# Proiect_TSC.net
KiCad netlist of a schematic drawn in EAGLE
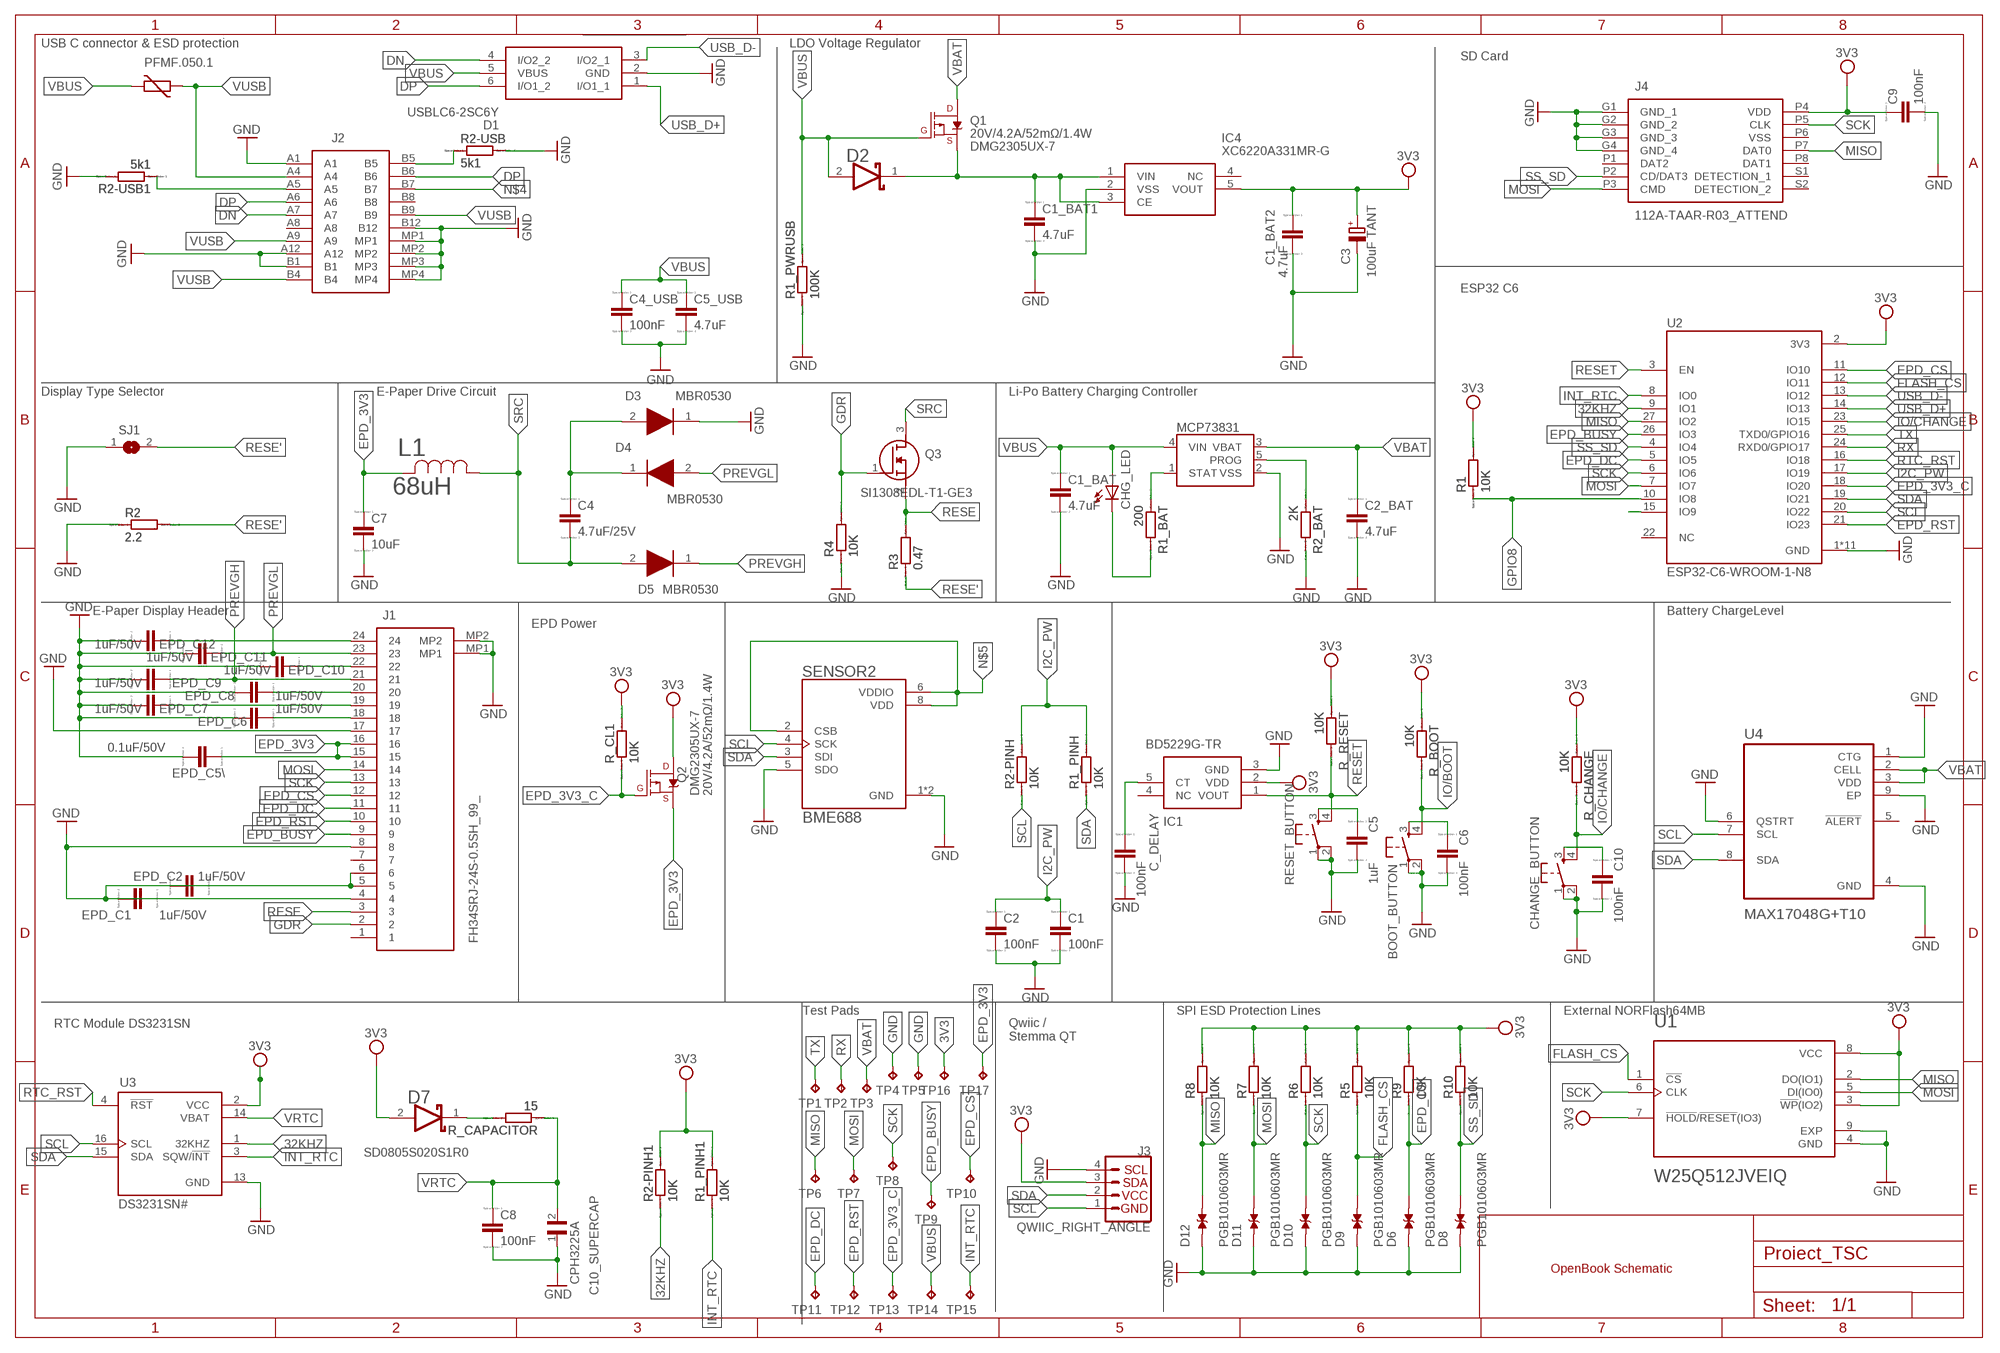
[diagram p0: schematic, sheet 1]

(export (version "E")
  (design (tool "Eeschema 10.0.6"))
  (components
    (comp (ref "BOOT_BUTTON")
      (value "BUTTON_CUSYOMV1")
      (footprint "eagle-import:MYBUTTON")
      (libsource (lib "eagle-import") (part "BUTTON_CUSYOMV1"))
    )
    (comp (ref "C1")
      (value "100nF")
      (footprint "eagle-import:ESP32_WROVER_EAGLE-LTSPICE_C0402")
      (libsource (lib "eagle-import") (part "ESP32_WROVER_EAGLE-LTSPICE_CC0402"))
    )
    (comp (ref "C1_BAT")
      (value "4.7uF")
      (footprint "eagle-import:ESP32_WROVER_EAGLE-LTSPICE_C0402")
      (libsource (lib "eagle-import") (part "ESP32_WROVER_EAGLE-LTSPICE_CC0402"))
    )
    (comp (ref "C1_BAT1")
      (value "4.7uF")
      (footprint "eagle-import:ESP32_WROVER_EAGLE-LTSPICE_C0402")
      (libsource (lib "eagle-import") (part "ESP32_WROVER_EAGLE-LTSPICE_CC0402"))
    )
    (comp (ref "C1_BAT2")
      (value "4.7uF")
      (footprint "eagle-import:ESP32_WROVER_EAGLE-LTSPICE_C0402")
      (libsource (lib "eagle-import") (part "ESP32_WROVER_EAGLE-LTSPICE_CC0402"))
    )
    (comp (ref "C2")
      (value "100nF")
      (footprint "eagle-import:ESP32_WROVER_EAGLE-LTSPICE_C0402")
      (libsource (lib "eagle-import") (part "ESP32_WROVER_EAGLE-LTSPICE_CC0402"))
    )
    (comp (ref "C2_BAT")
      (value "4.7uF")
      (footprint "eagle-import:ESP32_WROVER_EAGLE-LTSPICE_C0402")
      (libsource (lib "eagle-import") (part "ESP32_WROVER_EAGLE-LTSPICE_CC0402"))
    )
    (comp (ref "C3")
      (value "100uF TANT")
      (footprint "eagle-import:RCL_CT3528")
      (libsource (lib "eagle-import") (part "RCL_CPOL-EUCT3528"))
    )
    (comp (ref "C4")
      (value "4.7uF/25V")
      (footprint "eagle-import:ESP32_WROVER_EAGLE-LTSPICE_C0402")
      (libsource (lib "eagle-import") (part "ESP32_WROVER_EAGLE-LTSPICE_CC0402"))
    )
    (comp (ref "C4_USB")
      (value "100nF")
      (footprint "eagle-import:ESP32_WROVER_EAGLE-LTSPICE_C0402")
      (libsource (lib "eagle-import") (part "ESP32_WROVER_EAGLE-LTSPICE_CC0402"))
    )
    (comp (ref "C5")
      (value "1uF")
      (footprint "eagle-import:ESP32_WROVER_EAGLE-LTSPICE_C0402")
      (libsource (lib "eagle-import") (part "ESP32_WROVER_EAGLE-LTSPICE_CC0402"))
    )
    (comp (ref "C5_USB")
      (value "4.7uF")
      (footprint "eagle-import:ESP32_WROVER_EAGLE-LTSPICE_C0402")
      (libsource (lib "eagle-import") (part "ESP32_WROVER_EAGLE-LTSPICE_CC0402"))
    )
    (comp (ref "C6")
      (value "100nF")
      (footprint "eagle-import:ESP32_WROVER_EAGLE-LTSPICE_C0402")
      (libsource (lib "eagle-import") (part "ESP32_WROVER_EAGLE-LTSPICE_CC0402"))
    )
    (comp (ref "C7")
      (value "10uF")
      (footprint "eagle-import:ESP32_WROVER_EAGLE-LTSPICE_C0402")
      (libsource (lib "eagle-import") (part "ESP32_WROVER_EAGLE-LTSPICE_CC0402"))
    )
    (comp (ref "C8")
      (value "100nF")
      (footprint "eagle-import:ESP32_WROVER_EAGLE-LTSPICE_C0402")
      (libsource (lib "eagle-import") (part "ESP32_WROVER_EAGLE-LTSPICE_CC0402"))
    )
    (comp (ref "C9")
      (value "100nF")
      (footprint "eagle-import:ESP32_WROVER_EAGLE-LTSPICE_C0402")
      (libsource (lib "eagle-import") (part "ESP32_WROVER_EAGLE-LTSPICE_CC0402"))
    )
    (comp (ref "C10")
      (value "100nF")
      (footprint "eagle-import:ESP32_WROVER_EAGLE-LTSPICE_C0402")
      (libsource (lib "eagle-import") (part "ESP32_WROVER_EAGLE-LTSPICE_CC0402"))
    )
    (comp (ref "C10_SUPERCAP")
      (value "CPH3225A")
      (footprint "eagle-import:CAPCP3225X100N")
      (fields (field (name "MF") "Seiko Instruments"))
      (libsource (lib "eagle-import") (part "CPH3225A"))
    )
    (comp (ref "CHANGE_BUTTON")
      (value "BUTTON_CUSYOMV1")
      (footprint "eagle-import:MYBUTTON")
      (libsource (lib "eagle-import") (part "BUTTON_CUSYOMV1"))
    )
    (comp (ref "CHG_LED")
      (value "ADAFRUIT_LEDCHIP-LED0603")
      (footprint "eagle-import:ADAFRUIT_CHIP-LED0603")
      (libsource (lib "eagle-import") (part "ADAFRUIT_LEDCHIP-LED0603"))
    )
    (comp (ref "C_DELAY")
      (value "100nF")
      (footprint "eagle-import:ESP32_WROVER_EAGLE-LTSPICE_C0402")
      (libsource (lib "eagle-import") (part "ESP32_WROVER_EAGLE-LTSPICE_CC0402"))
    )
    (comp (ref "D1")
      (value "USBLC6-2SC6Y")
      (footprint "eagle-import:SOT95P280X145-6N")
      (fields (field (name "MF") "STMicroelectronics"))
      (libsource (lib "eagle-import") (part "USBLC6-2SC6Y"))
    )
    (comp (ref "D2")
      (value "ESP32_WROVER_AVX---SD0805S020S1R0_AVX_SD0805S020S1R0_0_0AVX_SD0805S020S1R0_0_0")
      (footprint "eagle-import:ESP32_WROVER_AVX---SD0805S020S1R0_AVX_SD0805S020S1R0_0")
      (fields
        (field (name "DIGIKEY_PART_NUMBER") "478-7800-1-ND")
        (field (name "MF") "AVX")
        (field (name "MOUSER_PART_NUMBER") "581-SD0805S020S1R0")
      )
      (libsource (lib "eagle-import") (part "ESP32_WROVER_AVX---SD0805S020S1R0_AVX_SD0805S020S1R0_0_0AVX_SD0805S020S1R0_0_0"))
    )
    (comp (ref "D3")
      (value "MBR0530")
      (footprint "eagle-import:SOD3716X135N")
      (fields (field (name "MF") "ON Semiconductor"))
      (libsource (lib "eagle-import") (part "MBR0530"))
    )
    (comp (ref "D4")
      (value "MBR0530")
      (footprint "eagle-import:SOD3716X135N")
      (fields (field (name "MF") "ON Semiconductor"))
      (libsource (lib "eagle-import") (part "MBR0530"))
    )
    (comp (ref "D5")
      (value "MBR0530")
      (footprint "eagle-import:SOD3716X135N")
      (fields (field (name "MF") "ON Semiconductor"))
      (libsource (lib "eagle-import") (part "MBR0530"))
    )
    (comp (ref "D6")
      (value "PGB1010603MR")
      (footprint "eagle-import:DIOC1608X36N")
      (fields (field (name "MF") "Littelfuse Inc."))
      (libsource (lib "eagle-import") (part "PGB1010603MR"))
    )
    (comp (ref "D7")
      (value "ESP32_WROVER_AVX---SD0805S020S1R0_AVX_SD0805S020S1R0_0_0AVX_SD0805S020S1R0_0_0")
      (footprint "eagle-import:ESP32_WROVER_AVX---SD0805S020S1R0_AVX_SD0805S020S1R0_0")
      (fields
        (field (name "DIGIKEY_PART_NUMBER") "478-7800-1-ND")
        (field (name "MF") "AVX")
        (field (name "MOUSER_PART_NUMBER") "581-SD0805S020S1R0")
      )
      (libsource (lib "eagle-import") (part "ESP32_WROVER_AVX---SD0805S020S1R0_AVX_SD0805S020S1R0_0_0AVX_SD0805S020S1R0_0_0"))
    )
    (comp (ref "D8")
      (value "PGB1010603MR")
      (footprint "eagle-import:DIOC1608X36N")
      (fields (field (name "MF") "Littelfuse Inc."))
      (libsource (lib "eagle-import") (part "PGB1010603MR"))
    )
    (comp (ref "D9")
      (value "PGB1010603MR")
      (footprint "eagle-import:DIOC1608X36N")
      (fields (field (name "MF") "Littelfuse Inc."))
      (libsource (lib "eagle-import") (part "PGB1010603MR"))
    )
    (comp (ref "D10")
      (value "PGB1010603MR")
      (footprint "eagle-import:DIOC1608X36N")
      (fields (field (name "MF") "Littelfuse Inc."))
      (libsource (lib "eagle-import") (part "PGB1010603MR"))
    )
    (comp (ref "D11")
      (value "PGB1010603MR")
      (footprint "eagle-import:DIOC1608X36N")
      (fields (field (name "MF") "Littelfuse Inc."))
      (libsource (lib "eagle-import") (part "PGB1010603MR"))
    )
    (comp (ref "D12")
      (value "PGB1010603MR")
      (footprint "eagle-import:DIOC1608X36N")
      (fields (field (name "MF") "Littelfuse Inc."))
      (libsource (lib "eagle-import") (part "PGB1010603MR"))
    )
    (comp (ref "EPD_C1")
      (value "1uF/50V")
      (footprint "eagle-import:ESP32_WROVER_EAGLE-LTSPICE_C0402")
      (libsource (lib "eagle-import") (part "ESP32_WROVER_EAGLE-LTSPICE_CC0402"))
    )
    (comp (ref "EPD_C2")
      (value "1uF/50V")
      (footprint "eagle-import:ESP32_WROVER_EAGLE-LTSPICE_C0402")
      (libsource (lib "eagle-import") (part "ESP32_WROVER_EAGLE-LTSPICE_CC0402"))
    )
    (comp (ref "EPD_C5\\")
      (value "0.1uF/50V")
      (footprint "eagle-import:EAGLE-LTSPICE_C0402")
      (libsource (lib "eagle-import") (part "EAGLE-LTSPICE_CC0402"))
    )
    (comp (ref "EPD_C6")
      (value "1uF/50V")
      (footprint "eagle-import:EAGLE-LTSPICE_C0402")
      (libsource (lib "eagle-import") (part "EAGLE-LTSPICE_CC0402"))
    )
    (comp (ref "EPD_C7")
      (value "1uF/50V")
      (footprint "eagle-import:EAGLE-LTSPICE_C0402")
      (libsource (lib "eagle-import") (part "EAGLE-LTSPICE_CC0402"))
    )
    (comp (ref "EPD_C8")
      (value "1uF/50V")
      (footprint "eagle-import:EAGLE-LTSPICE_C0402")
      (libsource (lib "eagle-import") (part "EAGLE-LTSPICE_CC0402"))
    )
    (comp (ref "EPD_C9")
      (value "1uF/50V")
      (footprint "eagle-import:EAGLE-LTSPICE_C0402")
      (libsource (lib "eagle-import") (part "EAGLE-LTSPICE_CC0402"))
    )
    (comp (ref "EPD_C10")
      (value "1uF/50V")
      (footprint "eagle-import:EAGLE-LTSPICE_C0402")
      (libsource (lib "eagle-import") (part "EAGLE-LTSPICE_CC0402"))
    )
    (comp (ref "EPD_C11")
      (value "1uF/50V")
      (footprint "eagle-import:EAGLE-LTSPICE_C0402")
      (libsource (lib "eagle-import") (part "EAGLE-LTSPICE_CC0402"))
    )
    (comp (ref "EPD_C12")
      (value "1uF/50V")
      (footprint "eagle-import:EAGLE-LTSPICE_C0402")
      (libsource (lib "eagle-import") (part "EAGLE-LTSPICE_CC0402"))
    )
    (comp (ref "IC1")
      (value "BD5229G-TR")
      (footprint "eagle-import:SOT95P280X125-5N")
      (fields (field (name "MOUSER_PART_NUMBER") "755-BD5229G-TR"))
      (libsource (lib "eagle-import") (part "BD5229G-TR"))
    )
    (comp (ref "IC4")
      (value "XC6220A331MR-G")
      (footprint "eagle-import:SOT95P280X120-5N")
      (fields (field (name "MOUSER_PART_NUMBER") "865-XC6220A331MR-G"))
      (libsource (lib "eagle-import") (part "XC6220A331MR-G"))
    )
    (comp (ref "J1")
      (value "FH34SRJ-24S-0.5SH_99_")
      (footprint "eagle-import:FH34SRJ24S05SH99")
      (fields
        (field (name "MANUFACTURER_PART_NUMBER") "FH34SRJ-24S-0.5SH(99)")
        (field (name "MOUSER_PART_NUMBER") "798-FH34SRJ24S05SH99")
      )
      (libsource (lib "eagle-import") (part "FH34SRJ-24S-0.5SH_99_"))
    )
    (comp (ref "J2")
      (value "SAMACSYS_PARTS_USB4110-GF-A")
      (footprint "eagle-import:SAMACSYS_PARTS_USB4110GFA")
      (fields
        (field (name "MANUFACTURER_PART_NUMBER") "USB4110-GF-A")
        (field (name "MOUSER_PART_NUMBER") "640-USB4110-GF-A")
      )
      (libsource (lib "eagle-import") (part "SAMACSYS_PARTS_USB4110-GF-A"))
    )
    (comp (ref "J3")
      (value "QWIIC_RIGHT_ANGLE")
      (footprint "eagle-import:JST04_1MM_RA")
      (libsource (lib "eagle-import") (part "QWIIC_CONNECTORJS-1MM"))
    )
    (comp (ref "J4")
      (value "112A-TAAR-R03_ATTEND")
      (footprint "eagle-import:112ATAARR03ATTEND")
      (fields (field (name "MANUFACTURER_PART_NUMBER") "112A-TAAR-R03 ATTEND"))
      (libsource (lib "eagle-import") (part "112A-TAAR-R03_ATTEND"))
    )
    (comp (ref "L1")
      (value "68uH")
      (footprint "eagle-import:IND_4828-WE-TPC_WRE")
      (fields
        (field (name "MANUFACTURER_PART_NUMBER") "744043680")
        (field (name "COPYRIGHT") "Copyright (C) 2024 Ultra Librarian. All rights reserved.")
      )
      (libsource (lib "eagle-import") (part "744043680IND_4828-WE-TPC_WRE"))
    )
    (comp (ref "MCP73831")
      (value "ESP32_WROVER_SPARKFUN-IC-POWER_MCP73831")
      (footprint "eagle-import:ESP32_WROVER_SPARKFUN-IC-POWER_SOT23-5")
      (libsource (lib "eagle-import") (part "ESP32_WROVER_SPARKFUN-IC-POWER_MCP73831"))
    )
    (comp (ref "PFMF.050.1")
      (value "ESP32C6_VARISTORCN1812")
      (footprint "eagle-import:ESP32C6_VARISTOR_CT_CN1812")
      (libsource (lib "eagle-import") (part "ESP32C6_VARISTORCN1812"))
    )
    (comp (ref "Q1")
      (value "20V/4.2A/52mΩ/1.4W")
      (footprint "eagle-import:ESP32_WROVER_SPARKFUN-DISCRETESEMI_SOT23-3")
      (libsource (lib "eagle-import") (part "ESP32_WROVER_SPARKFUN-DISCRETESEMI_MOSFET_PCH-DMG2305UX-7"))
    )
    (comp (ref "Q2")
      (value "20V/4.2A/52mΩ/1.4W")
      (footprint "eagle-import:ESP32_WROVER_SPARKFUN-DISCRETESEMI_SOT23-3")
      (libsource (lib "eagle-import") (part "ESP32_WROVER_SPARKFUN-DISCRETESEMI_MOSFET_PCH-DMG2305UX-7"))
    )
    (comp (ref "Q3")
      (value "SI1308EDL-T1-GE3")
      (footprint "eagle-import:SOT65P210X110-3N")
      (fields (field (name "MF") "Vishay Siliconix"))
      (libsource (lib "eagle-import") (part "SI1308EDL-T1-GE3"))
    )
    (comp (ref "R1")
      (value "10K")
      (footprint "eagle-import:ESP32_WROVER_EAGLE-LTSPICE_R0402")
      (libsource (lib "eagle-import") (part "ESP32_WROVER_EAGLE-LTSPICE_RR0402"))
    )
    (comp (ref "R1_BAT")
      (value "200")
      (footprint "eagle-import:ESP32_WROVER_EAGLE-LTSPICE_R0402")
      (libsource (lib "eagle-import") (part "ESP32_WROVER_EAGLE-LTSPICE_RR0402"))
    )
    (comp (ref "R1_PINH")
      (value "10K")
      (footprint "eagle-import:ESP32_WROVER_EAGLE-LTSPICE_R0402")
      (libsource (lib "eagle-import") (part "ESP32_WROVER_EAGLE-LTSPICE_RR0402"))
    )
    (comp (ref "R1_PINH1")
      (value "10K")
      (footprint "eagle-import:ESP32_WROVER_EAGLE-LTSPICE_R0402")
      (libsource (lib "eagle-import") (part "ESP32_WROVER_EAGLE-LTSPICE_RR0402"))
    )
    (comp (ref "R1_PWRUSB")
      (value "100K")
      (footprint "eagle-import:ESP32_WROVER_EAGLE-LTSPICE_R0402")
      (libsource (lib "eagle-import") (part "ESP32_WROVER_EAGLE-LTSPICE_RR0402"))
    )
    (comp (ref "R2")
      (value "2.2")
      (footprint "eagle-import:ESP32_WROVER_EAGLE-LTSPICE_R0402")
      (libsource (lib "eagle-import") (part "ESP32_WROVER_EAGLE-LTSPICE_RR0402"))
    )
    (comp (ref "R2-PINH")
      (value "10K")
      (footprint "eagle-import:ESP32_WROVER_EAGLE-LTSPICE_R0402")
      (libsource (lib "eagle-import") (part "ESP32_WROVER_EAGLE-LTSPICE_RR0402"))
    )
    (comp (ref "R2-PINH1")
      (value "10K")
      (footprint "eagle-import:ESP32_WROVER_EAGLE-LTSPICE_R0402")
      (libsource (lib "eagle-import") (part "ESP32_WROVER_EAGLE-LTSPICE_RR0402"))
    )
    (comp (ref "R2-USB")
      (value "5k1")
      (footprint "eagle-import:ESP32_WROVER_EAGLE-LTSPICE_R0402")
      (libsource (lib "eagle-import") (part "ESP32_WROVER_EAGLE-LTSPICE_RR0402"))
    )
    (comp (ref "R2-USB1")
      (value "5k1")
      (footprint "eagle-import:ESP32_WROVER_EAGLE-LTSPICE_R0402")
      (libsource (lib "eagle-import") (part "ESP32_WROVER_EAGLE-LTSPICE_RR0402"))
    )
    (comp (ref "R2_BAT")
      (value "2K")
      (footprint "eagle-import:ESP32_WROVER_EAGLE-LTSPICE_R0402")
      (libsource (lib "eagle-import") (part "ESP32_WROVER_EAGLE-LTSPICE_RR0402"))
    )
    (comp (ref "R3")
      (value "0.47")
      (footprint "eagle-import:ESP32_WROVER_EAGLE-LTSPICE_R0402")
      (libsource (lib "eagle-import") (part "ESP32_WROVER_EAGLE-LTSPICE_RR0402"))
    )
    (comp (ref "R4")
      (value "10K")
      (footprint "eagle-import:ESP32_WROVER_EAGLE-LTSPICE_R0402")
      (libsource (lib "eagle-import") (part "ESP32_WROVER_EAGLE-LTSPICE_RR0402"))
    )
    (comp (ref "R5")
      (value "10K")
      (footprint "eagle-import:ESP32_WROVER_EAGLE-LTSPICE_R0402")
      (libsource (lib "eagle-import") (part "ESP32_WROVER_EAGLE-LTSPICE_RR0402"))
    )
    (comp (ref "R6")
      (value "10K")
      (footprint "eagle-import:ESP32_WROVER_EAGLE-LTSPICE_R0402")
      (libsource (lib "eagle-import") (part "ESP32_WROVER_EAGLE-LTSPICE_RR0402"))
    )
    (comp (ref "R7")
      (value "10K")
      (footprint "eagle-import:ESP32_WROVER_EAGLE-LTSPICE_R0402")
      (libsource (lib "eagle-import") (part "ESP32_WROVER_EAGLE-LTSPICE_RR0402"))
    )
    (comp (ref "R8")
      (value "10K")
      (footprint "eagle-import:ESP32_WROVER_EAGLE-LTSPICE_R0402")
      (libsource (lib "eagle-import") (part "ESP32_WROVER_EAGLE-LTSPICE_RR0402"))
    )
    (comp (ref "R9")
      (value "10K")
      (footprint "eagle-import:ESP32_WROVER_EAGLE-LTSPICE_R0402")
      (libsource (lib "eagle-import") (part "ESP32_WROVER_EAGLE-LTSPICE_RR0402"))
    )
    (comp (ref "R10")
      (value "10K")
      (footprint "eagle-import:ESP32_WROVER_EAGLE-LTSPICE_R0402")
      (libsource (lib "eagle-import") (part "ESP32_WROVER_EAGLE-LTSPICE_RR0402"))
    )
    (comp (ref "RESET_BUTTON")
      (value "BUTTON_CUSYOMV1")
      (footprint "eagle-import:MYBUTTON")
      (libsource (lib "eagle-import") (part "BUTTON_CUSYOMV1"))
    )
    (comp (ref "R_BOOT")
      (value "10K")
      (footprint "eagle-import:ESP32_WROVER_EAGLE-LTSPICE_R0402")
      (libsource (lib "eagle-import") (part "ESP32_WROVER_EAGLE-LTSPICE_RR0402"))
    )
    (comp (ref "R_CAPACITOR")
      (value "15")
      (footprint "eagle-import:ESP32_WROVER_EAGLE-LTSPICE_R0402")
      (libsource (lib "eagle-import") (part "ESP32_WROVER_EAGLE-LTSPICE_RR0402"))
    )
    (comp (ref "R_CHANGE")
      (value "10K")
      (footprint "eagle-import:ESP32_WROVER_EAGLE-LTSPICE_R0402")
      (libsource (lib "eagle-import") (part "ESP32_WROVER_EAGLE-LTSPICE_RR0402"))
    )
    (comp (ref "R_CL1")
      (value "10K")
      (footprint "eagle-import:ESP32_WROVER_EAGLE-LTSPICE_R0402")
      (libsource (lib "eagle-import") (part "ESP32_WROVER_EAGLE-LTSPICE_RR0402"))
    )
    (comp (ref "R_RESET")
      (value "10K")
      (footprint "eagle-import:ESP32_WROVER_EAGLE-LTSPICE_R0402")
      (libsource (lib "eagle-import") (part "ESP32_WROVER_EAGLE-LTSPICE_RR0402"))
    )
    (comp (ref "SENSOR2")
      (value "BME688")
      (footprint "eagle-import:ESP32_WROVER_BME680_PSON80P300X300X100-8N")
      (fields (field (name "MF") "Bosch Sensortec") (field (name "MP") "BME680"))
      (libsource (lib "eagle-import") (part "ESP32_WROVER_BME680_BME680"))
    )
    (comp (ref "SJ1") (value "SJ") (footprint "eagle-import:SJ") (libsource (lib "eagle-import") (part "SJ")))
    (comp (ref "TP1")
      (value "TPTP20R")
      (footprint "eagle-import:TP20R")
      (libsource (lib "eagle-import") (part "TPTP20R"))
    )
    (comp (ref "TP2")
      (value "TPTP20R")
      (footprint "eagle-import:TP20R")
      (libsource (lib "eagle-import") (part "TPTP20R"))
    )
    (comp (ref "TP3")
      (value "TPTP20R")
      (footprint "eagle-import:TP20R")
      (libsource (lib "eagle-import") (part "TPTP20R"))
    )
    (comp (ref "TP4")
      (value "TPTP20R")
      (footprint "eagle-import:TP20R")
      (libsource (lib "eagle-import") (part "TPTP20R"))
    )
    (comp (ref "TP5")
      (value "TPTP20R")
      (footprint "eagle-import:TP20R")
      (libsource (lib "eagle-import") (part "TPTP20R"))
    )
    (comp (ref "TP6")
      (value "TPTP20R")
      (footprint "eagle-import:TP20R")
      (libsource (lib "eagle-import") (part "TPTP20R"))
    )
    (comp (ref "TP7")
      (value "TPTP20R")
      (footprint "eagle-import:TP20R")
      (libsource (lib "eagle-import") (part "TPTP20R"))
    )
    (comp (ref "TP8")
      (value "TPTP20R")
      (footprint "eagle-import:TP20R")
      (libsource (lib "eagle-import") (part "TPTP20R"))
    )
    (comp (ref "TP9")
      (value "TPTP20R")
      (footprint "eagle-import:TP20R")
      (libsource (lib "eagle-import") (part "TPTP20R"))
    )
    (comp (ref "TP10")
      (value "TPTP20R")
      (footprint "eagle-import:TP20R")
      (libsource (lib "eagle-import") (part "TPTP20R"))
    )
    (comp (ref "TP11")
      (value "TPTP20R")
      (footprint "eagle-import:TP20R")
      (libsource (lib "eagle-import") (part "TPTP20R"))
    )
    (comp (ref "TP12")
      (value "TPTP20R")
      (footprint "eagle-import:TP20R")
      (libsource (lib "eagle-import") (part "TPTP20R"))
    )
    (comp (ref "TP13")
      (value "TPTP20R")
      (footprint "eagle-import:TP20R")
      (libsource (lib "eagle-import") (part "TPTP20R"))
    )
    (comp (ref "TP14")
      (value "TPTP20R")
      (footprint "eagle-import:TP20R")
      (libsource (lib "eagle-import") (part "TPTP20R"))
    )
    (comp (ref "TP15")
      (value "TPTP20R")
      (footprint "eagle-import:TP20R")
      (libsource (lib "eagle-import") (part "TPTP20R"))
    )
    (comp (ref "TP16")
      (value "TPTP20R")
      (footprint "eagle-import:TP20R")
      (libsource (lib "eagle-import") (part "TPTP20R"))
    )
    (comp (ref "TP17")
      (value "TPTP20R")
      (footprint "eagle-import:TP20R")
      (libsource (lib "eagle-import") (part "TPTP20R"))
    )
    (comp (ref "U1")
      (value "W25Q512JVEIQ")
      (footprint "eagle-import:SON127P600X800X80-9N")
      (fields (field (name "MF") "Winbond Electronics"))
      (libsource (lib "eagle-import") (part "W25Q512JVEIQ"))
    )
    (comp (ref "U2")
      (value "ESP32-C6-WROOM-1-N8")
      (footprint "eagle-import:XCVR_ESP32-C6-WROOM-1-N8")
      (fields (field (name "MF") "Espressif Systems"))
      (libsource (lib "eagle-import") (part "ESP32-C6-WROOM-1-N8"))
    )
    (comp (ref "U3")
      (value "DS3231SN#")
      (footprint "eagle-import:SOIC127P1032X265-16N")
      (fields (field (name "MF") "Analog Devices"))
      (libsource (lib "eagle-import") (part "DS3231SN#"))
    )
    (comp (ref "U4")
      (value "MAX17048G+T10")
      (footprint "eagle-import:SON50P200X200X80-9N")
      (fields (field (name "MF") "Analog Devices"))
      (libsource (lib "eagle-import") (part "MAX17048G+T10"))
    )
  )
  (nets
    (net (code "1") (name "3V3") (class "Default")
      (node (ref "C1_BAT2") (pin "1") (pinfunction "1_1") (pintype "passive"))
      (node (ref "C3") (pin "+") (pinfunction "+_+") (pintype "passive"))
      (node (ref "C9") (pin "1") (pinfunction "1_1") (pintype "passive"))
      (node (ref "D7") (pin "2") (pinfunction "ANODE_2") (pintype "bidirectional"))
      (node (ref "IC1") (pin "2") (pinfunction "VDD_2") (pintype "bidirectional"))
      (node (ref "IC4") (pin "5") (pinfunction "VOUT_5") (pintype "bidirectional"))
      (node (ref "J3") (pin "3") (pinfunction "3_3") (pintype "passive"))
      (node (ref "J4") (pin "P4") (pinfunction "VDD_P4") (pintype "bidirectional"))
      (node (ref "Q2") (pin "3") (pinfunction "D_3") (pintype "bidirectional"))
      (node (ref "R1") (pin "2") (pinfunction "2_2") (pintype "passive"))
      (node (ref "R10") (pin "2") (pinfunction "2_2") (pintype "passive"))
      (node (ref "R1_PINH1") (pin "2") (pinfunction "2_2") (pintype "passive"))
      (node (ref "R2-PINH1") (pin "2") (pinfunction "2_2") (pintype "passive"))
      (node (ref "R5") (pin "2") (pinfunction "2_2") (pintype "passive"))
      (node (ref "R6") (pin "2") (pinfunction "2_2") (pintype "passive"))
      (node (ref "R7") (pin "2") (pinfunction "2_2") (pintype "passive"))
      (node (ref "R8") (pin "2") (pinfunction "2_2") (pintype "passive"))
      (node (ref "R9") (pin "2") (pinfunction "2_2") (pintype "passive"))
      (node (ref "R_BOOT") (pin "1") (pinfunction "1_1") (pintype "passive"))
      (node (ref "R_CHANGE") (pin "1") (pinfunction "1_1") (pintype "passive"))
      (node (ref "R_CL1") (pin "2") (pinfunction "2_2") (pintype "passive"))
      (node (ref "R_RESET") (pin "1") (pinfunction "1_1") (pintype "passive"))
      (node (ref "TP16") (pin "TP") (pinfunction "TP_TP") (pintype "input"))
      (node (ref "U1") (pin "3") (pinfunction "~{WP}(IO2)_3") (pintype "bidirectional"))
      (node (ref "U1") (pin "7") (pinfunction "~{HOLD}/~{RESET}(IO3)_7") (pintype "bidirectional"))
      (node (ref "U1") (pin "8") (pinfunction "VCC_8") (pintype "power_in"))
      (node (ref "U2") (pin "2") (pinfunction "3V3_2") (pintype "power_in"))
      (node (ref "U3") (pin "2") (pinfunction "VCC_2") (pintype "power_in"))
    )
    (net (code "2") (name "32KHZ") (class "Default")
      (node (ref "R2-PINH1") (pin "1") (pinfunction "1_1") (pintype "passive"))
      (node (ref "U2") (pin "9") (pinfunction "IO1_9") (pintype "bidirectional"))
      (node (ref "U3") (pin "1") (pinfunction "32KHZ_1") (pintype "output"))
    )
    (net (code "3") (name "DN") (class "Default")
      (node (ref "D1") (pin "4") (pinfunction "I/O2_2_4") (pintype "bidirectional"))
      (node (ref "J2") (pin "A7") (pinfunction "A7_A7") (pintype "bidirectional"))
    )
    (net (code "4") (name "DP") (class "Default")
      (node (ref "D1") (pin "6") (pinfunction "I/O1_2_6") (pintype "bidirectional"))
      (node (ref "J2") (pin "A6") (pinfunction "A6_A6") (pintype "bidirectional"))
      (node (ref "J2") (pin "B6") (pinfunction "B6_B6") (pintype "bidirectional"))
    )
    (net (code "5") (name "EPD_3V3") (class "Default")
      (node (ref "C7") (pin "1") (pinfunction "1_1") (pintype "passive"))
      (node (ref "EPD_C5\\") (pin "1") (pinfunction "1_1") (pintype "passive"))
      (node (ref "J1") (pin "15") (pinfunction "15_15") (pintype "bidirectional"))
      (node (ref "J1") (pin "16") (pinfunction "16_16") (pintype "bidirectional"))
      (node (ref "L1") (pin "2") (pinfunction "2_2") (pintype "passive"))
      (node (ref "Q2") (pin "2") (pinfunction "S_2") (pintype "bidirectional"))
      (node (ref "TP17") (pin "TP") (pinfunction "TP_TP") (pintype "input"))
    )
    (net (code "6") (name "EPD_3V3_C") (class "Default")
      (node (ref "Q2") (pin "1") (pinfunction "G_1") (pintype "bidirectional"))
      (node (ref "R_CL1") (pin "1") (pinfunction "1_1") (pintype "passive"))
      (node (ref "TP13") (pin "TP") (pinfunction "TP_TP") (pintype "input"))
      (node (ref "U2") (pin "18") (pinfunction "IO20_18") (pintype "bidirectional"))
    )
    (net (code "7") (name "EPD_BUSY") (class "Default")
      (node (ref "J1") (pin "9") (pinfunction "9_9") (pintype "bidirectional"))
      (node (ref "TP9") (pin "TP") (pinfunction "TP_TP") (pintype "input"))
      (node (ref "U2") (pin "26") (pinfunction "IO3_26") (pintype "bidirectional"))
    )
    (net (code "8") (name "EPD_CS") (class "Default")
      (node (ref "D6") (pin "2") (pinfunction "2_2") (pintype "passive"))
      (node (ref "J1") (pin "12") (pinfunction "12_12") (pintype "bidirectional"))
      (node (ref "R9") (pin "1") (pinfunction "1_1") (pintype "passive"))
      (node (ref "TP10") (pin "TP") (pinfunction "TP_TP") (pintype "input"))
      (node (ref "U2") (pin "11") (pinfunction "IO10_11") (pintype "bidirectional"))
    )
    (net (code "9") (name "EPD_DC") (class "Default")
      (node (ref "J1") (pin "11") (pinfunction "11_11") (pintype "bidirectional"))
      (node (ref "TP11") (pin "TP") (pinfunction "TP_TP") (pintype "input"))
      (node (ref "U2") (pin "5") (pinfunction "IO5_5") (pintype "bidirectional"))
    )
    (net (code "10") (name "EPD_RST") (class "Default")
      (node (ref "J1") (pin "10") (pinfunction "10_10") (pintype "bidirectional"))
      (node (ref "TP12") (pin "TP") (pinfunction "TP_TP") (pintype "input"))
      (node (ref "U2") (pin "21") (pinfunction "IO23_21") (pintype "bidirectional"))
    )
    (net (code "11") (name "FLASH_CS") (class "Default")
      (node (ref "D9") (pin "2") (pinfunction "2_2") (pintype "passive"))
      (node (ref "R5") (pin "1") (pinfunction "1_1") (pintype "passive"))
      (node (ref "U1") (pin "1") (pinfunction "~{CS}_1") (pintype "input"))
      (node (ref "U2") (pin "12") (pinfunction "IO11_12") (pintype "bidirectional"))
    )
    (net (code "12") (name "GDR") (class "Default")
      (node (ref "J1") (pin "2") (pinfunction "2_2") (pintype "bidirectional"))
      (node (ref "Q3") (pin "1") (pinfunction "G_1") (pintype "bidirectional"))
      (node (ref "R4") (pin "2") (pinfunction "2_2") (pintype "passive"))
    )
    (net (code "13") (name "GND") (class "Default")
      (node (ref "BOOT_BUTTON") (pin "2") (pinfunction "2_2") (pintype "passive"))
      (node (ref "C1") (pin "2") (pinfunction "2_2") (pintype "passive"))
      (node (ref "C10") (pin "2") (pinfunction "2_2") (pintype "passive"))
      (node (ref "C10_SUPERCAP") (pin "1") (pinfunction "1_1") (pintype "passive"))
      (node (ref "C1_BAT") (pin "2") (pinfunction "2_2") (pintype "passive"))
      (node (ref "C1_BAT1") (pin "2") (pinfunction "2_2") (pintype "passive"))
      (node (ref "C1_BAT2") (pin "2") (pinfunction "2_2") (pintype "passive"))
      (node (ref "C2") (pin "2") (pinfunction "2_2") (pintype "passive"))
      (node (ref "C2_BAT") (pin "2") (pinfunction "2_2") (pintype "passive"))
      (node (ref "C3") (pin "-") (pinfunction "-_-") (pintype "passive"))
      (node (ref "C4_USB") (pin "2") (pinfunction "2_2") (pintype "passive"))
      (node (ref "C5") (pin "2") (pinfunction "2_2") (pintype "passive"))
      (node (ref "C5_USB") (pin "2") (pinfunction "2_2") (pintype "passive"))
      (node (ref "C6") (pin "2") (pinfunction "2_2") (pintype "passive"))
      (node (ref "C7") (pin "2") (pinfunction "2_2") (pintype "passive"))
      (node (ref "C8") (pin "2") (pinfunction "2_2") (pintype "passive"))
      (node (ref "C9") (pin "2") (pinfunction "2_2") (pintype "passive"))
      (node (ref "CHANGE_BUTTON") (pin "2") (pinfunction "2_2") (pintype "passive"))
      (node (ref "C_DELAY") (pin "2") (pinfunction "2_2") (pintype "passive"))
      (node (ref "D1") (pin "2") (pinfunction "GND_2") (pintype "bidirectional"))
      (node (ref "D10") (pin "1") (pinfunction "1_1") (pintype "passive"))
      (node (ref "D11") (pin "1") (pinfunction "1_1") (pintype "passive"))
      (node (ref "D12") (pin "1") (pinfunction "1_1") (pintype "passive"))
      (node (ref "D3") (pin "1") (pinfunction "K_1") (pintype "bidirectional"))
      (node (ref "D6") (pin "1") (pinfunction "1_1") (pintype "passive"))
      (node (ref "D8") (pin "1") (pinfunction "1_1") (pintype "passive"))
      (node (ref "D9") (pin "1") (pinfunction "1_1") (pintype "passive"))
      (node (ref "EPD_C1") (pin "1") (pinfunction "1_1") (pintype "passive"))
      (node (ref "EPD_C10") (pin "2") (pinfunction "2_2") (pintype "passive"))
      (node (ref "EPD_C11") (pin "2") (pinfunction "2_2") (pintype "passive"))
      (node (ref "EPD_C12") (pin "2") (pinfunction "2_2") (pintype "passive"))
      (node (ref "EPD_C2") (pin "1") (pinfunction "1_1") (pintype "passive"))
      (node (ref "EPD_C5\\") (pin "2") (pinfunction "2_2") (pintype "passive"))
      (node (ref "EPD_C6") (pin "2") (pinfunction "2_2") (pintype "passive"))
      (node (ref "EPD_C7") (pin "2") (pinfunction "2_2") (pintype "passive"))
      (node (ref "EPD_C8") (pin "2") (pinfunction "2_2") (pintype "passive"))
      (node (ref "EPD_C9") (pin "2") (pinfunction "2_2") (pintype "passive"))
      (node (ref "IC1") (pin "3") (pinfunction "GND_3") (pintype "bidirectional"))
      (node (ref "IC4") (pin "2") (pinfunction "VSS_2") (pintype "bidirectional"))
      (node (ref "J1") (pin "17") (pinfunction "17_17") (pintype "bidirectional"))
      (node (ref "J1") (pin "8") (pinfunction "8_8") (pintype "bidirectional"))
      (node (ref "J1") (pin "MP1") (pinfunction "MP1_MP1") (pintype "bidirectional"))
      (node (ref "J1") (pin "MP2") (pinfunction "MP2_MP2") (pintype "bidirectional"))
      (node (ref "J2") (pin "A1") (pinfunction "A1_A1") (pintype "bidirectional"))
      (node (ref "J2") (pin "A12") (pinfunction "A12_A12") (pintype "bidirectional"))
      (node (ref "J2") (pin "B1") (pinfunction "B1_B1") (pintype "bidirectional"))
      (node (ref "J2") (pin "B12") (pinfunction "B12_B12") (pintype "bidirectional"))
      (node (ref "J2") (pin "MP1") (pinfunction "MP1_MP1") (pintype "bidirectional"))
      (node (ref "J2") (pin "MP2") (pinfunction "MP2_MP2") (pintype "bidirectional"))
      (node (ref "J2") (pin "MP3") (pinfunction "MP3_MP3") (pintype "bidirectional"))
      (node (ref "J2") (pin "MP4") (pinfunction "MP4_MP4") (pintype "bidirectional"))
      (node (ref "J3") (pin "4") (pinfunction "4_4") (pintype "passive"))
      (node (ref "J4") (pin "G1") (pinfunction "GND_1_G1") (pintype "bidirectional"))
      (node (ref "J4") (pin "G2") (pinfunction "GND_2_G2") (pintype "bidirectional"))
      (node (ref "J4") (pin "G3") (pinfunction "GND_3_G3") (pintype "bidirectional"))
      (node (ref "J4") (pin "G4") (pinfunction "GND_4_G4") (pintype "bidirectional"))
      (node (ref "MCP73831") (pin "2") (pinfunction "VSS_2") (pintype "power_in"))
      (node (ref "R1_PWRUSB") (pin "1") (pinfunction "1_1") (pintype "passive"))
      (node (ref "R2") (pin "1") (pinfunction "1_1") (pintype "passive"))
      (node (ref "R2-USB") (pin "2") (pinfunction "2_2") (pintype "passive"))
      (node (ref "R2-USB1") (pin "2") (pinfunction "2_2") (pintype "passive"))
      (node (ref "R2_BAT") (pin "2") (pinfunction "2_2") (pintype "passive"))
      (node (ref "R4") (pin "1") (pinfunction "1_1") (pintype "passive"))
      (node (ref "RESET_BUTTON") (pin "1") (pinfunction "1_1") (pintype "passive"))
      (node (ref "RESET_BUTTON") (pin "2") (pinfunction "2_2") (pintype "passive"))
      (node (ref "SENSOR2") (pin "1") (pinfunction "GND_1") (pintype "power_in"))
      (node (ref "SENSOR2") (pin "5") (pinfunction "SDO_5") (pintype "bidirectional"))
      (node (ref "SENSOR2") (pin "7") (pinfunction "GND_7") (pintype "power_in"))
      (node (ref "SJ1") (pin "1") (pinfunction "1_1") (pintype "passive"))
      (node (ref "TP4") (pin "TP") (pinfunction "TP_TP") (pintype "input"))
      (node (ref "TP5") (pin "TP") (pinfunction "TP_TP") (pintype "input"))
      (node (ref "U1") (pin "4") (pinfunction "GND_4") (pintype "power_in"))
      (node (ref "U1") (pin "9") (pinfunction "EXP_9") (pintype "passive"))
      (node (ref "U2") (pin "1") (pinfunction "GND_1") (pintype "power_in"))
      (node (ref "U2") (pin "28") (pinfunction "GND_28") (pintype "power_in"))
      (node (ref "U2") (pin "29_1") (pinfunction "GND_29_1") (pintype "power_in"))
      (node (ref "U2") (pin "29_2") (pinfunction "GND_29_2") (pintype "power_in"))
      (node (ref "U2") (pin "29_3") (pinfunction "GND_29_3") (pintype "power_in"))
      (node (ref "U2") (pin "29_4") (pinfunction "GND_29_4") (pintype "power_in"))
      (node (ref "U2") (pin "29_5") (pinfunction "GND_29_5") (pintype "power_in"))
      (node (ref "U2") (pin "29_6") (pinfunction "GND_29_6") (pintype "power_in"))
      (node (ref "U2") (pin "29_7") (pinfunction "GND_29_7") (pintype "power_in"))
      (node (ref "U2") (pin "29_8") (pinfunction "GND_29_8") (pintype "power_in"))
      (node (ref "U2") (pin "29_9") (pinfunction "GND_29_9") (pintype "power_in"))
      (node (ref "U3") (pin "13") (pinfunction "GND_13") (pintype "power_in"))
      (node (ref "U4") (pin "1") (pinfunction "CTG_1") (pintype "power_in"))
      (node (ref "U4") (pin "4") (pinfunction "GND_4") (pintype "power_in"))
      (node (ref "U4") (pin "6") (pinfunction "QSTRT_6") (pintype "input"))
      (node (ref "U4") (pin "9") (pinfunction "EP_9") (pintype "power_in"))
    )
    (net (code "14") (name "GPIO8") (class "Default")
      (node (ref "R1") (pin "1") (pinfunction "1_1") (pintype "passive"))
      (node (ref "U2") (pin "10") (pinfunction "IO8_10") (pintype "bidirectional"))
    )
    (net (code "15") (name "I2C_PW") (class "Default")
      (node (ref "C1") (pin "1") (pinfunction "1_1") (pintype "passive"))
      (node (ref "C2") (pin "1") (pinfunction "1_1") (pintype "passive"))
      (node (ref "R1_PINH") (pin "2") (pinfunction "2_2") (pintype "passive"))
      (node (ref "R2-PINH") (pin "2") (pinfunction "2_2") (pintype "passive"))
      (node (ref "U2") (pin "17") (pinfunction "IO19_17") (pintype "bidirectional"))
    )
    (net (code "16") (name "INT_RTC") (class "Default")
      (node (ref "R1_PINH1") (pin "1") (pinfunction "1_1") (pintype "passive"))
      (node (ref "TP15") (pin "TP") (pinfunction "TP_TP") (pintype "input"))
      (node (ref "U2") (pin "8") (pinfunction "IO0_8") (pintype "bidirectional"))
      (node (ref "U3") (pin "3") (pinfunction "SQW/~{INT}_3") (pintype "output"))
    )
    (net (code "17") (name "IO{slash}BOOT") (class "Default")
      (node (ref "BOOT_BUTTON") (pin "4") (pinfunction "4_4") (pintype "passive"))
      (node (ref "R_BOOT") (pin "2") (pinfunction "2_2") (pintype "passive"))
    )
    (net (code "18") (name "IO{slash}CHANGE") (class "Default")
      (node (ref "CHANGE_BUTTON") (pin "4") (pinfunction "4_4") (pintype "passive"))
      (node (ref "R_CHANGE") (pin "2") (pinfunction "2_2") (pintype "passive"))
      (node (ref "U2") (pin "23") (pinfunction "IO15_23") (pintype "bidirectional"))
    )
    (net (code "19") (name "MISO") (class "Default")
      (node (ref "D12") (pin "2") (pinfunction "2_2") (pintype "passive"))
      (node (ref "J4") (pin "P7") (pinfunction "DAT0_P7") (pintype "bidirectional"))
      (node (ref "R8") (pin "1") (pinfunction "1_1") (pintype "passive"))
      (node (ref "TP6") (pin "TP") (pinfunction "TP_TP") (pintype "input"))
      (node (ref "U1") (pin "2") (pinfunction "DO(IO1)_2") (pintype "bidirectional"))
      (node (ref "U2") (pin "27") (pinfunction "IO2_27") (pintype "bidirectional"))
    )
    (net (code "20") (name "MOSI") (class "Default")
      (node (ref "D11") (pin "2") (pinfunction "2_2") (pintype "passive"))
      (node (ref "J1") (pin "14") (pinfunction "14_14") (pintype "bidirectional"))
      (node (ref "J4") (pin "P3") (pinfunction "CMD_P3") (pintype "bidirectional"))
      (node (ref "R7") (pin "1") (pinfunction "1_1") (pintype "passive"))
      (node (ref "TP7") (pin "TP") (pinfunction "TP_TP") (pintype "input"))
      (node (ref "U1") (pin "5") (pinfunction "DI(IO0)_5") (pintype "bidirectional"))
      (node (ref "U2") (pin "7") (pinfunction "IO7_7") (pintype "bidirectional"))
    )
    (net (code "21") (name "N$4") (class "Default")
      (node (ref "J2") (pin "B7") (pinfunction "B7_B7") (pintype "bidirectional"))
    )
    (net (code "22") (name "N$5") (class "Default")
      (node (ref "SENSOR2") (pin "2") (pinfunction "CSB_2") (pintype "input"))
      (node (ref "SENSOR2") (pin "6") (pinfunction "VDDIO_6") (pintype "power_in"))
      (node (ref "SENSOR2") (pin "8") (pinfunction "VDD_8") (pintype "power_in"))
    )
    (net (code "23") (name "Net-(BOOT_BUTTON-Pad3)") (class "Default")
      (node (ref "BOOT_BUTTON") (pin "3") (pinfunction "3_3") (pintype "passive"))
      (node (ref "C6") (pin "1") (pinfunction "1_1") (pintype "passive"))
    )
    (net (code "24") (name "Net-(C5-Pad1)") (class "Default")
      (node (ref "C5") (pin "1") (pinfunction "1_1") (pintype "passive"))
      (node (ref "RESET_BUTTON") (pin "3") (pinfunction "3_3") (pintype "passive"))
    )
    (net (code "25") (name "Net-(C10-Pad1)") (class "Default")
      (node (ref "C10") (pin "1") (pinfunction "1_1") (pintype "passive"))
      (node (ref "CHANGE_BUTTON") (pin "3") (pinfunction "3_3") (pintype "passive"))
    )
    (net (code "26") (name "Net-(CHG_LED-PadC)") (class "Default")
      (node (ref "CHG_LED") (pin "C") (pinfunction "C_C") (pintype "passive"))
      (node (ref "R1_BAT") (pin "2") (pinfunction "2_2") (pintype "passive"))
    )
    (net (code "27") (name "Net-(D2-CATHODE)") (class "Default")
      (node (ref "C1_BAT1") (pin "1") (pinfunction "1_1") (pintype "passive"))
      (node (ref "D2") (pin "1") (pinfunction "CATHODE_1") (pintype "bidirectional"))
      (node (ref "IC4") (pin "1") (pinfunction "VIN_1") (pintype "bidirectional"))
      (node (ref "IC4") (pin "3") (pinfunction "CE_3") (pintype "bidirectional"))
      (node (ref "Q1") (pin "2") (pinfunction "S_2") (pintype "bidirectional"))
    )
    (net (code "28") (name "Net-(D3-A)") (class "Default")
      (node (ref "C4") (pin "1") (pinfunction "1_1") (pintype "passive"))
      (node (ref "D3") (pin "2") (pinfunction "A_2") (pintype "bidirectional"))
      (node (ref "D4") (pin "1") (pinfunction "K_1") (pintype "bidirectional"))
    )
    (net (code "29") (name "Net-(D7-CATHODE)") (class "Default")
      (node (ref "D7") (pin "1") (pinfunction "CATHODE_1") (pintype "bidirectional"))
      (node (ref "R_CAPACITOR") (pin "2") (pinfunction "2_2") (pintype "passive"))
    )
    (net (code "30") (name "Net-(EPD_C1-Pad2)") (class "Default")
      (node (ref "EPD_C1") (pin "2") (pinfunction "2_2") (pintype "passive"))
      (node (ref "J1") (pin "4") (pinfunction "4_4") (pintype "bidirectional"))
    )
    (net (code "31") (name "Net-(EPD_C2-Pad2)") (class "Default")
      (node (ref "EPD_C2") (pin "2") (pinfunction "2_2") (pintype "passive"))
      (node (ref "J1") (pin "5") (pinfunction "5_5") (pintype "bidirectional"))
      (node (ref "J1") (pin "6") (pinfunction "6_6") (pintype "bidirectional"))
    )
    (net (code "32") (name "Net-(EPD_C6-Pad1)") (class "Default")
      (node (ref "EPD_C6") (pin "1") (pinfunction "1_1") (pintype "passive"))
      (node (ref "J1") (pin "18") (pinfunction "18_18") (pintype "bidirectional"))
    )
    (net (code "33") (name "Net-(EPD_C7-Pad1)") (class "Default")
      (node (ref "EPD_C7") (pin "1") (pinfunction "1_1") (pintype "passive"))
      (node (ref "J1") (pin "19") (pinfunction "19_19") (pintype "bidirectional"))
    )
    (net (code "34") (name "Net-(EPD_C8-Pad1)") (class "Default")
      (node (ref "EPD_C8") (pin "1") (pinfunction "1_1") (pintype "passive"))
      (node (ref "J1") (pin "20") (pinfunction "20_20") (pintype "bidirectional"))
    )
    (net (code "35") (name "Net-(EPD_C10-Pad1)") (class "Default")
      (node (ref "EPD_C10") (pin "1") (pinfunction "1_1") (pintype "passive"))
      (node (ref "J1") (pin "22") (pinfunction "22_22") (pintype "bidirectional"))
    )
    (net (code "36") (name "Net-(EPD_C12-Pad1)") (class "Default")
      (node (ref "EPD_C12") (pin "1") (pinfunction "1_1") (pintype "passive"))
      (node (ref "J1") (pin "24") (pinfunction "24_24") (pintype "bidirectional"))
    )
    (net (code "37") (name "Net-(IC1-CT)") (class "Default")
      (node (ref "C_DELAY") (pin "1") (pinfunction "1_1") (pintype "passive"))
      (node (ref "IC1") (pin "5") (pinfunction "CT_5") (pintype "bidirectional"))
    )
    (net (code "38") (name "Net-(J2-PadA5)") (class "Default")
      (node (ref "J2") (pin "A5") (pinfunction "A5_A5") (pintype "bidirectional"))
      (node (ref "R2-USB1") (pin "1") (pinfunction "1_1") (pintype "passive"))
    )
    (net (code "39") (name "Net-(J2-PadB5)") (class "Default")
      (node (ref "J2") (pin "B5") (pinfunction "B5_B5") (pintype "bidirectional"))
      (node (ref "R2-USB") (pin "1") (pinfunction "1_1") (pintype "passive"))
    )
    (net (code "40") (name "Net-(MCP73831-PROG)") (class "Default")
      (node (ref "MCP73831") (pin "5") (pinfunction "PROG_5") (pintype "input"))
      (node (ref "R2_BAT") (pin "1") (pinfunction "1_1") (pintype "passive"))
    )
    (net (code "41") (name "Net-(MCP73831-STAT)") (class "Default")
      (node (ref "MCP73831") (pin "1") (pinfunction "STAT_1") (pintype "output"))
      (node (ref "R1_BAT") (pin "1") (pinfunction "1_1") (pintype "passive"))
    )
    (net (code "42") (name "PREVGH") (class "Default")
      (node (ref "D5") (pin "1") (pinfunction "K_1") (pintype "bidirectional"))
      (node (ref "EPD_C9") (pin "1") (pinfunction "1_1") (pintype "passive"))
      (node (ref "J1") (pin "21") (pinfunction "21_21") (pintype "bidirectional"))
    )
    (net (code "43") (name "PREVGL") (class "Default")
      (node (ref "D4") (pin "2") (pinfunction "A_2") (pintype "bidirectional"))
      (node (ref "EPD_C11") (pin "1") (pinfunction "1_1") (pintype "passive"))
      (node (ref "J1") (pin "23") (pinfunction "23_23") (pintype "bidirectional"))
    )
    (net (code "44") (name "RESE") (class "Default")
      (node (ref "J1") (pin "3") (pinfunction "3_3") (pintype "bidirectional"))
      (node (ref "Q3") (pin "2") (pinfunction "S_2") (pintype "bidirectional"))
      (node (ref "R3") (pin "2") (pinfunction "2_2") (pintype "passive"))
    )
    (net (code "45") (name "RESE'") (class "Default")
      (node (ref "R2") (pin "2") (pinfunction "2_2") (pintype "passive"))
      (node (ref "R3") (pin "1") (pinfunction "1_1") (pintype "passive"))
      (node (ref "SJ1") (pin "2") (pinfunction "2_2") (pintype "passive"))
    )
    (net (code "46") (name "RESET") (class "Default")
      (node (ref "IC1") (pin "1") (pinfunction "VOUT_1") (pintype "bidirectional"))
      (node (ref "RESET_BUTTON") (pin "4") (pinfunction "4_4") (pintype "passive"))
      (node (ref "R_RESET") (pin "2") (pinfunction "2_2") (pintype "passive"))
      (node (ref "U2") (pin "3") (pinfunction "EN_3") (pintype "input"))
    )
    (net (code "47") (name "RTC_RST") (class "Default")
      (node (ref "U2") (pin "16") (pinfunction "IO18_16") (pintype "bidirectional"))
      (node (ref "U3") (pin "4") (pinfunction "~{RST}_4") (pintype "input"))
    )
    (net (code "48") (name "RX") (class "Default")
      (node (ref "TP2") (pin "TP") (pinfunction "TP_TP") (pintype "input"))
      (node (ref "U2") (pin "24") (pinfunction "RXD0/GPIO17_24") (pintype "bidirectional"))
    )
    (net (code "49") (name "SCK") (class "Default")
      (node (ref "D10") (pin "2") (pinfunction "2_2") (pintype "passive"))
      (node (ref "J1") (pin "13") (pinfunction "13_13") (pintype "bidirectional"))
      (node (ref "J4") (pin "P5") (pinfunction "CLK_P5") (pintype "bidirectional"))
      (node (ref "R6") (pin "1") (pinfunction "1_1") (pintype "passive"))
      (node (ref "TP8") (pin "TP") (pinfunction "TP_TP") (pintype "input"))
      (node (ref "U1") (pin "6") (pinfunction "CLK_6") (pintype "input"))
      (node (ref "U2") (pin "6") (pinfunction "IO6_6") (pintype "bidirectional"))
    )
    (net (code "50") (name "SCL") (class "Default")
      (node (ref "J3") (pin "1") (pinfunction "1_1") (pintype "power_in"))
      (node (ref "R2-PINH") (pin "1") (pinfunction "1_1") (pintype "passive"))
      (node (ref "SENSOR2") (pin "4") (pinfunction "SCK_4") (pintype "input"))
      (node (ref "U2") (pin "20") (pinfunction "IO22_20") (pintype "bidirectional"))
      (node (ref "U3") (pin "16") (pinfunction "SCL_16") (pintype "input"))
      (node (ref "U4") (pin "7") (pinfunction "SCL_7") (pintype "input"))
    )
    (net (code "51") (name "SDA") (class "Default")
      (node (ref "J3") (pin "2") (pinfunction "2_2") (pintype "power_in"))
      (node (ref "R1_PINH") (pin "1") (pinfunction "1_1") (pintype "passive"))
      (node (ref "SENSOR2") (pin "3") (pinfunction "SDI_3") (pintype "bidirectional"))
      (node (ref "U2") (pin "19") (pinfunction "IO21_19") (pintype "bidirectional"))
      (node (ref "U3") (pin "15") (pinfunction "SDA_15") (pintype "bidirectional"))
      (node (ref "U4") (pin "8") (pinfunction "SDA_8") (pintype "bidirectional"))
    )
    (net (code "52") (name "SRC") (class "Default")
      (node (ref "C4") (pin "2") (pinfunction "2_2") (pintype "passive"))
      (node (ref "D5") (pin "2") (pinfunction "A_2") (pintype "bidirectional"))
      (node (ref "L1") (pin "1") (pinfunction "1_1") (pintype "passive"))
      (node (ref "Q3") (pin "3") (pinfunction "D_3") (pintype "bidirectional"))
    )
    (net (code "53") (name "SS_SD") (class "Default")
      (node (ref "D8") (pin "2") (pinfunction "2_2") (pintype "passive"))
      (node (ref "J4") (pin "P2") (pinfunction "CD/DAT3_P2") (pintype "bidirectional"))
      (node (ref "R10") (pin "1") (pinfunction "1_1") (pintype "passive"))
      (node (ref "U2") (pin "4") (pinfunction "IO4_4") (pintype "bidirectional"))
    )
    (net (code "54") (name "TX") (class "Default")
      (node (ref "TP1") (pin "TP") (pinfunction "TP_TP") (pintype "input"))
      (node (ref "U2") (pin "25") (pinfunction "TXD0/GPIO16_25") (pintype "bidirectional"))
    )
    (net (code "55") (name "USB_D+") (class "Default")
      (node (ref "D1") (pin "1") (pinfunction "I/O1_1_1") (pintype "bidirectional"))
      (node (ref "U2") (pin "14") (pinfunction "IO13_14") (pintype "bidirectional"))
    )
    (net (code "56") (name "USB_D-") (class "Default")
      (node (ref "D1") (pin "3") (pinfunction "I/O2_1_3") (pintype "bidirectional"))
      (node (ref "U2") (pin "13") (pinfunction "IO12_13") (pintype "bidirectional"))
    )
    (net (code "57") (name "VBAT") (class "Default")
      (node (ref "C2_BAT") (pin "1") (pinfunction "1_1") (pintype "passive"))
      (node (ref "MCP73831") (pin "3") (pinfunction "VBAT_3") (pintype "power_in"))
      (node (ref "Q1") (pin "3") (pinfunction "D_3") (pintype "bidirectional"))
      (node (ref "TP3") (pin "TP") (pinfunction "TP_TP") (pintype "input"))
      (node (ref "U4") (pin "2") (pinfunction "CELL_2") (pintype "power_in"))
      (node (ref "U4") (pin "3") (pinfunction "VDD_3") (pintype "power_in"))
    )
    (net (code "58") (name "VBUS") (class "Default")
      (node (ref "C1_BAT") (pin "1") (pinfunction "1_1") (pintype "passive"))
      (node (ref "C4_USB") (pin "1") (pinfunction "1_1") (pintype "passive"))
      (node (ref "C5_USB") (pin "1") (pinfunction "1_1") (pintype "passive"))
      (node (ref "CHG_LED") (pin "A") (pinfunction "A_A") (pintype "passive"))
      (node (ref "D1") (pin "5") (pinfunction "VBUS_5") (pintype "bidirectional"))
      (node (ref "D2") (pin "2") (pinfunction "ANODE_2") (pintype "bidirectional"))
      (node (ref "MCP73831") (pin "4") (pinfunction "VIN_4") (pintype "power_in"))
      (node (ref "PFMF.050.1") (pin "2") (pinfunction "2_2") (pintype "passive"))
      (node (ref "Q1") (pin "1") (pinfunction "G_1") (pintype "bidirectional"))
      (node (ref "R1_PWRUSB") (pin "2") (pinfunction "2_2") (pintype "passive"))
      (node (ref "TP14") (pin "TP") (pinfunction "TP_TP") (pintype "input"))
    )
    (net (code "59") (name "VRTC") (class "Default")
      (node (ref "C10_SUPERCAP") (pin "2") (pinfunction "2_2") (pintype "passive"))
      (node (ref "C8") (pin "1") (pinfunction "1_1") (pintype "passive"))
      (node (ref "R_CAPACITOR") (pin "1") (pinfunction "1_1") (pintype "passive"))
      (node (ref "U3") (pin "14") (pinfunction "VBAT_14") (pintype "power_in"))
    )
    (net (code "60") (name "VUSB") (class "Default")
      (node (ref "J2") (pin "A4") (pinfunction "A4_A4") (pintype "bidirectional"))
      (node (ref "J2") (pin "A9") (pinfunction "A9_A9") (pintype "bidirectional"))
      (node (ref "J2") (pin "B4") (pinfunction "B4_B4") (pintype "bidirectional"))
      (node (ref "J2") (pin "B9") (pinfunction "B9_B9") (pintype "bidirectional"))
      (node (ref "PFMF.050.1") (pin "1") (pinfunction "1_1") (pintype "passive"))
    )
    (net (code "61") (name "unconnected-(BOOT_BUTTON-Pad1)") (class "Default")
      (node (ref "BOOT_BUTTON") (pin "1") (pinfunction "1_1") (pintype "passive"))
    )
    (net (code "62") (name "unconnected-(CHANGE_BUTTON-Pad1)") (class "Default")
      (node (ref "CHANGE_BUTTON") (pin "1") (pinfunction "1_1") (pintype "passive"))
    )
    (net (code "63") (name "unconnected-(IC1-NC-Pad4)") (class "Default")
      (node (ref "IC1") (pin "4") (pinfunction "NC_4") (pintype "no_connect"))
    )
    (net (code "64") (name "unconnected-(IC4-NC-Pad4)") (class "Default")
      (node (ref "IC4") (pin "4") (pinfunction "NC_4") (pintype "no_connect"))
    )
    (net (code "65") (name "unconnected-(J1-Pad1)") (class "Default")
      (node (ref "J1") (pin "1") (pinfunction "1_1") (pintype "bidirectional"))
    )
    (net (code "66") (name "unconnected-(J1-Pad7)") (class "Default")
      (node (ref "J1") (pin "7") (pinfunction "7_7") (pintype "bidirectional"))
    )
    (net (code "67") (name "unconnected-(J2-PadA8)") (class "Default")
      (node (ref "J2") (pin "A8") (pinfunction "A8_A8") (pintype "bidirectional"))
    )
    (net (code "68") (name "unconnected-(J2-PadB8)") (class "Default")
      (node (ref "J2") (pin "B8") (pinfunction "B8_B8") (pintype "bidirectional"))
    )
    (net (code "69") (name "unconnected-(J4-DAT1-PadP8)") (class "Default")
      (node (ref "J4") (pin "P8") (pinfunction "DAT1_P8") (pintype "bidirectional"))
    )
    (net (code "70") (name "unconnected-(J4-DAT2-PadP1)") (class "Default")
      (node (ref "J4") (pin "P1") (pinfunction "DAT2_P1") (pintype "bidirectional"))
    )
    (net (code "71") (name "unconnected-(J4-DETECTION_1-PadS1)") (class "Default")
      (node (ref "J4") (pin "S1") (pinfunction "DETECTION_1_S1") (pintype "bidirectional"))
    )
    (net (code "72") (name "unconnected-(J4-DETECTION_2-PadS2)") (class "Default")
      (node (ref "J4") (pin "S2") (pinfunction "DETECTION_2_S2") (pintype "bidirectional"))
    )
    (net (code "73") (name "unconnected-(J4-VSS-PadP6)") (class "Default")
      (node (ref "J4") (pin "P6") (pinfunction "VSS_P6") (pintype "bidirectional"))
    )
    (net (code "74") (name "unconnected-(U2-IO9-Pad15)") (class "Default")
      (node (ref "U2") (pin "15") (pinfunction "IO9_15") (pintype "bidirectional"))
    )
    (net (code "75") (name "unconnected-(U2-NC-Pad22)") (class "Default")
      (node (ref "U2") (pin "22") (pinfunction "NC_22") (pintype "no_connect"))
    )
    (net (code "76") (name "unconnected-(U4-~{ALERT}-Pad5)") (class "Default")
      (node (ref "U4") (pin "5") (pinfunction "~{ALERT}_5") (pintype "output"))
    )
  )
)
